# LVDS.net
KiCad netlist of a schematic drawn in Altium Designer
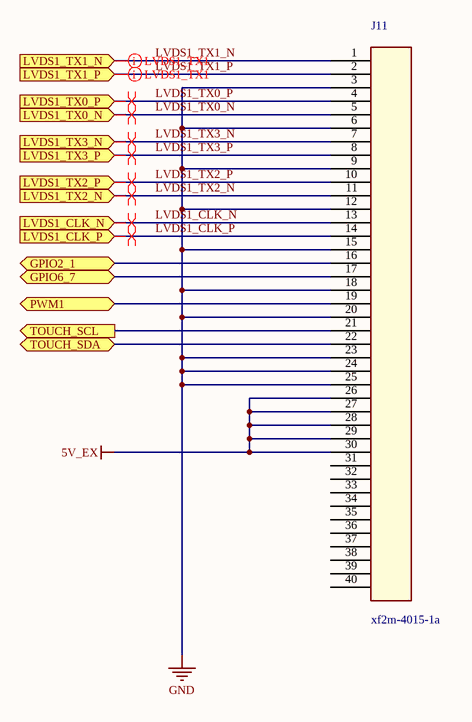
[diagram p0: LVDS.SchDoc]

(export (version "E")
  (design (tool "Eeschema 10.0.6"))
  (components
    (comp (ref "J11")
      (value "xf2m-4015-1a")
      (footprint "FPC40-0P5-OMRON")
      (libsource (lib "MY-I.MX6-SCH_Library") (part "CON40"))
    )
  )
  (nets
    (net (code "1") (name "/GPIO2_1") (class "Default")
      (node (ref "J11") (pin "16") (pinfunction "16_16") (pintype "passive"))
    )
    (net (code "2") (name "/GPIO6_7") (class "Default")
      (node (ref "J11") (pin "17") (pinfunction "17_17") (pintype "passive"))
    )
    (net (code "3") (name "/LVDS1_CLK_N") (class "Default")
      (node (ref "J11") (pin "13") (pinfunction "13_13") (pintype "passive"))
    )
    (net (code "4") (name "/LVDS1_CLK_P") (class "Default")
      (node (ref "J11") (pin "14") (pinfunction "14_14") (pintype "passive"))
    )
    (net (code "5") (name "/LVDS1_TX0_N") (class "Default")
      (node (ref "J11") (pin "5") (pinfunction "5_5") (pintype "passive"))
    )
    (net (code "6") (name "/LVDS1_TX0_P") (class "Default")
      (node (ref "J11") (pin "4") (pinfunction "4_4") (pintype "passive"))
    )
    (net (code "7") (name "/LVDS1_TX1_N") (class "Default")
      (node (ref "J11") (pin "1") (pinfunction "1_1") (pintype "passive"))
    )
    (net (code "8") (name "/LVDS1_TX1_P") (class "Default")
      (node (ref "J11") (pin "2") (pinfunction "2_2") (pintype "passive"))
    )
    (net (code "9") (name "/LVDS1_TX2_N") (class "Default")
      (node (ref "J11") (pin "11") (pinfunction "11_11") (pintype "passive"))
    )
    (net (code "10") (name "/LVDS1_TX2_P") (class "Default")
      (node (ref "J11") (pin "10") (pinfunction "10_10") (pintype "passive"))
    )
    (net (code "11") (name "/LVDS1_TX3_N") (class "Default")
      (node (ref "J11") (pin "7") (pinfunction "7_7") (pintype "passive"))
    )
    (net (code "12") (name "/LVDS1_TX3_P") (class "Default")
      (node (ref "J11") (pin "8") (pinfunction "8_8") (pintype "passive"))
    )
    (net (code "13") (name "/PWM1") (class "Default")
      (node (ref "J11") (pin "19") (pinfunction "19_19") (pintype "passive"))
    )
    (net (code "14") (name "/TOUCH_SCL") (class "Default")
      (node (ref "J11") (pin "21") (pinfunction "21_21") (pintype "passive"))
    )
    (net (code "15") (name "/TOUCH_SDA") (class "Default")
      (node (ref "J11") (pin "22") (pinfunction "22_22") (pintype "passive"))
    )
    (net (code "16") (name "5V_EX") (class "Default")
      (node (ref "J11") (pin "26") (pinfunction "26_26") (pintype "passive"))
      (node (ref "J11") (pin "27") (pinfunction "27_27") (pintype "passive"))
      (node (ref "J11") (pin "28") (pinfunction "28_28") (pintype "passive"))
      (node (ref "J11") (pin "29") (pinfunction "29_29") (pintype "passive"))
      (node (ref "J11") (pin "30") (pinfunction "30_30") (pintype "passive"))
    )
    (net (code "17") (name "GND") (class "Default")
      (node (ref "J11") (pin "12") (pinfunction "12_12") (pintype "passive"))
      (node (ref "J11") (pin "15") (pinfunction "15_15") (pintype "passive"))
      (node (ref "J11") (pin "18") (pinfunction "18_18") (pintype "passive"))
      (node (ref "J11") (pin "20") (pinfunction "20_20") (pintype "passive"))
      (node (ref "J11") (pin "23") (pinfunction "23_23") (pintype "passive"))
      (node (ref "J11") (pin "24") (pinfunction "24_24") (pintype "passive"))
      (node (ref "J11") (pin "25") (pinfunction "25_25") (pintype "passive"))
      (node (ref "J11") (pin "3") (pinfunction "3_3") (pintype "passive"))
      (node (ref "J11") (pin "6") (pinfunction "6_6") (pintype "passive"))
      (node (ref "J11") (pin "9") (pinfunction "9_9") (pintype "passive"))
    )
    (net (code "18") (name "unconnected-(J11-Pad31)") (class "Default")
      (node (ref "J11") (pin "31") (pinfunction "31_31") (pintype "passive"))
    )
    (net (code "19") (name "unconnected-(J11-Pad32)") (class "Default")
      (node (ref "J11") (pin "32") (pinfunction "32_32") (pintype "passive"))
    )
    (net (code "20") (name "unconnected-(J11-Pad33)") (class "Default")
      (node (ref "J11") (pin "33") (pinfunction "33_33") (pintype "passive"))
    )
    (net (code "21") (name "unconnected-(J11-Pad34)") (class "Default")
      (node (ref "J11") (pin "34") (pinfunction "34_34") (pintype "passive"))
    )
    (net (code "22") (name "unconnected-(J11-Pad35)") (class "Default")
      (node (ref "J11") (pin "35") (pinfunction "35_35") (pintype "passive"))
    )
    (net (code "23") (name "unconnected-(J11-Pad36)") (class "Default")
      (node (ref "J11") (pin "36") (pinfunction "36_36") (pintype "passive"))
    )
    (net (code "24") (name "unconnected-(J11-Pad37)") (class "Default")
      (node (ref "J11") (pin "37") (pinfunction "37_37") (pintype "passive"))
    )
    (net (code "25") (name "unconnected-(J11-Pad38)") (class "Default")
      (node (ref "J11") (pin "38") (pinfunction "38_38") (pintype "passive"))
    )
    (net (code "26") (name "unconnected-(J11-Pad39)") (class "Default")
      (node (ref "J11") (pin "39") (pinfunction "39_39") (pintype "passive"))
    )
    (net (code "27") (name "unconnected-(J11-Pad40)") (class "Default")
      (node (ref "J11") (pin "40") (pinfunction "40_40") (pintype "passive"))
    )
  )
)
